# codelock.net
KiCad netlist of a schematic drawn in EAGLE
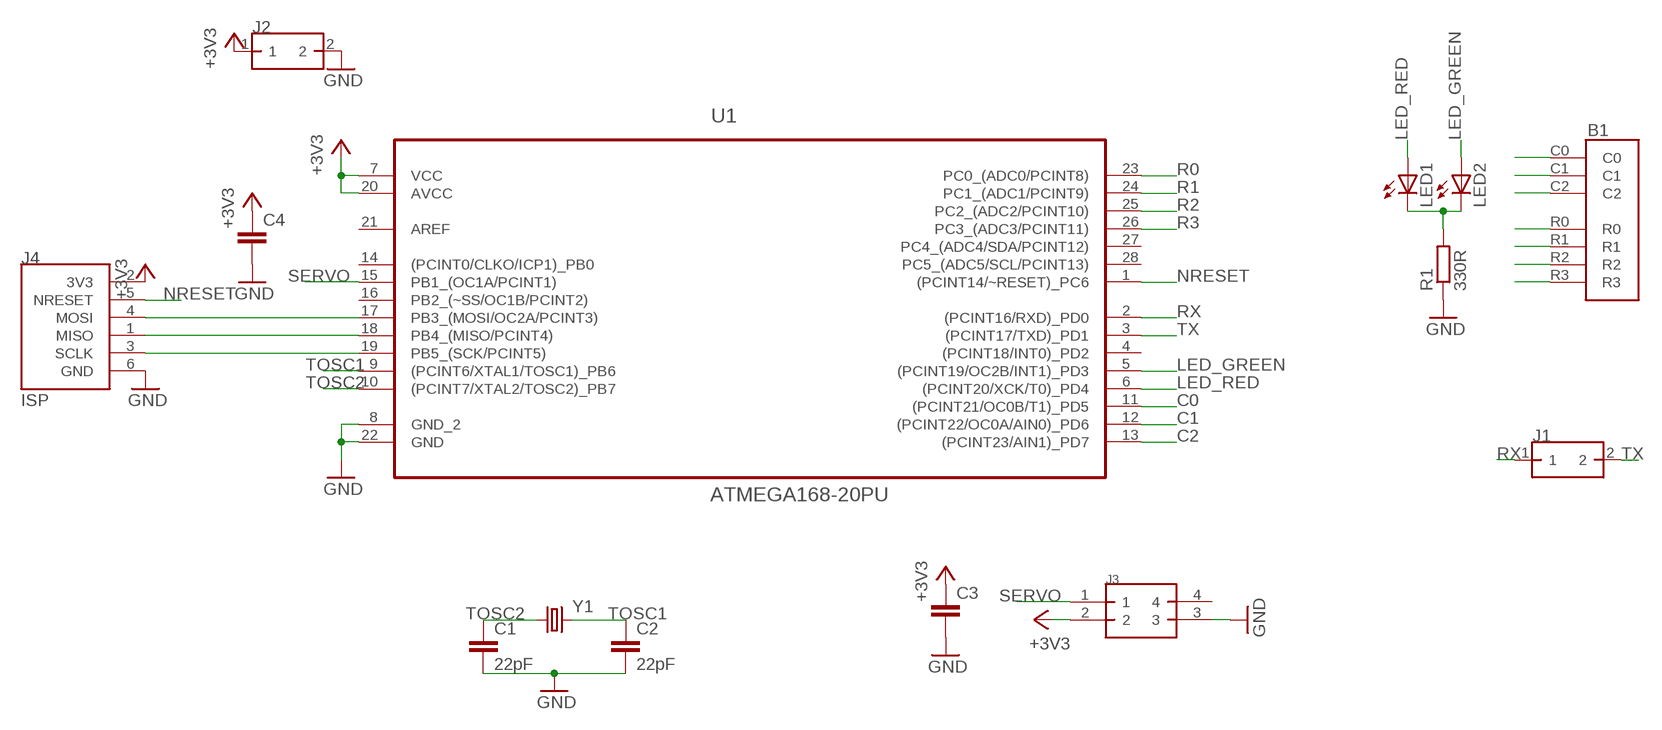
[diagram p0: schematic, sheet 1]

(export (version "E")
  (design (tool "Eeschema 10.0.6"))
  (components
    (comp (ref "B1")
      (value "KEYPAD12")
      (footprint "eagle-import:KEYPAD12")
      (libsource (lib "eagle-import") (part "KEYPAD12"))
    )
    (comp (ref "C1")
      (value "22pF")
      (footprint "eagle-import:C025-024X044")
      (libsource (lib "eagle-import") (part "C-EU025-024X044"))
    )
    (comp (ref "C2")
      (value "22pF")
      (footprint "eagle-import:C025-024X044")
      (libsource (lib "eagle-import") (part "C-EU025-024X044"))
    )
    (comp (ref "C3")
      (value "C-EU025-024X044")
      (footprint "eagle-import:C025-024X044")
      (libsource (lib "eagle-import") (part "C-EU025-024X044"))
    )
    (comp (ref "C4")
      (value "C-EU025-024X044")
      (footprint "eagle-import:C025-024X044")
      (libsource (lib "eagle-import") (part "C-EU025-024X044"))
    )
    (comp (ref "J1")
      (value "1BY2THROUGHHOLE")
      (footprint "eagle-import:1BY2")
      (libsource (lib "eagle-import") (part "1BY2THROUGHHOLE"))
    )
    (comp (ref "J2")
      (value "1BY2THROUGHHOLE")
      (footprint "eagle-import:1BY2")
      (libsource (lib "eagle-import") (part "1BY2THROUGHHOLE"))
    )
    (comp (ref "J3")
      (value "4PIN2.54MM1X4TH")
      (footprint "eagle-import:2.54MM1X4TH")
      (libsource (lib "eagle-import") (part "4PIN2.54MM1X4TH"))
    )
    (comp (ref "J4")
      (value "ISP")
      (footprint "eagle-import:DUALHEAD_TH_6")
      (libsource (lib "eagle-import") (part "ISP"))
    )
    (comp (ref "LED1")
      (value "LED3MM")
      (footprint "eagle-import:LED3MM")
      (libsource (lib "eagle-import") (part "LED3MM"))
    )
    (comp (ref "LED2")
      (value "LED3MM")
      (footprint "eagle-import:LED3MM")
      (libsource (lib "eagle-import") (part "LED3MM"))
    )
    (comp (ref "R1")
      (value "330R")
      (footprint "eagle-import:V234_12")
      (libsource (lib "eagle-import") (part "R12MM"))
    )
    (comp (ref "U1")
      (value "ATMEGA168-20PU")
      (footprint "eagle-import:DIP254P762X457-28")
      (libsource (lib "eagle-import") (part "ATMEGA168-20PU"))
    )
    (comp (ref "Y1")
      (value "CRYSTALHC49US")
      (footprint "eagle-import:HC49US")
      (libsource (lib "eagle-import") (part "CRYSTALHC49US"))
    )
  )
  (nets
    (net (code "1") (name "+3V3") (class "Default")
      (node (ref "C3") (pin "1") (pinfunction "1_1") (pintype "passive"))
      (node (ref "C4") (pin "1") (pinfunction "1_1") (pintype "passive"))
      (node (ref "J2") (pin "1") (pinfunction "1_1") (pintype "bidirectional"))
      (node (ref "J3") (pin "2") (pinfunction "2_2") (pintype "bidirectional"))
      (node (ref "J4") (pin "2") (pinfunction "3V3_2") (pintype "power_in"))
      (node (ref "U1") (pin "20") (pinfunction "AVCC_20") (pintype "power_in"))
      (node (ref "U1") (pin "7") (pinfunction "VCC_7") (pintype "power_in"))
    )
    (net (code "2") (name "/C0") (class "Default")
      (node (ref "B1") (pin "C0") (pinfunction "C0_C0") (pintype "bidirectional"))
      (node (ref "U1") (pin "11") (pinfunction "(PCINT21/OC0B/T1)_PD5_11") (pintype "bidirectional"))
    )
    (net (code "3") (name "/C1") (class "Default")
      (node (ref "B1") (pin "C1") (pinfunction "C1_C1") (pintype "bidirectional"))
      (node (ref "U1") (pin "12") (pinfunction "(PCINT22/OC0A/AIN0)_PD6_12") (pintype "bidirectional"))
    )
    (net (code "4") (name "/C2") (class "Default")
      (node (ref "B1") (pin "C2") (pinfunction "C2_C2") (pintype "bidirectional"))
      (node (ref "U1") (pin "13") (pinfunction "(PCINT23/AIN1)_PD7_13") (pintype "bidirectional"))
    )
    (net (code "5") (name "/LED_GREEN") (class "Default")
      (node (ref "LED2") (pin "A") (pinfunction "A_A") (pintype "passive"))
      (node (ref "U1") (pin "5") (pinfunction "(PCINT19/OC2B/INT1)_PD3_5") (pintype "bidirectional"))
    )
    (net (code "6") (name "/LED_RED") (class "Default")
      (node (ref "LED1") (pin "A") (pinfunction "A_A") (pintype "passive"))
      (node (ref "U1") (pin "6") (pinfunction "(PCINT20/XCK/T0)_PD4_6") (pintype "bidirectional"))
    )
    (net (code "7") (name "/NRESET") (class "Default")
      (node (ref "J4") (pin "5") (pinfunction "NRESET_5") (pintype "output"))
      (node (ref "U1") (pin "1") (pinfunction "(PCINT14/~{RESET})_PC6_1") (pintype "bidirectional"))
    )
    (net (code "8") (name "/R0") (class "Default")
      (node (ref "B1") (pin "R0") (pinfunction "R0_R0") (pintype "bidirectional"))
      (node (ref "U1") (pin "23") (pinfunction "PC0_(ADC0/PCINT8)_23") (pintype "bidirectional"))
    )
    (net (code "9") (name "/R1") (class "Default")
      (node (ref "B1") (pin "R1") (pinfunction "R1_R1") (pintype "bidirectional"))
      (node (ref "U1") (pin "24") (pinfunction "PC1_(ADC1/PCINT9)_24") (pintype "bidirectional"))
    )
    (net (code "10") (name "/R2") (class "Default")
      (node (ref "B1") (pin "R2") (pinfunction "R2_R2") (pintype "bidirectional"))
      (node (ref "U1") (pin "25") (pinfunction "PC2_(ADC2/PCINT10)_25") (pintype "bidirectional"))
    )
    (net (code "11") (name "/R3") (class "Default")
      (node (ref "B1") (pin "R3") (pinfunction "R3_R3") (pintype "bidirectional"))
      (node (ref "U1") (pin "26") (pinfunction "PC3_(ADC3/PCINT11)_26") (pintype "bidirectional"))
    )
    (net (code "12") (name "/RX") (class "Default")
      (node (ref "J1") (pin "1") (pinfunction "1_1") (pintype "bidirectional"))
      (node (ref "U1") (pin "2") (pinfunction "(PCINT16/RXD)_PD0_2") (pintype "bidirectional"))
    )
    (net (code "13") (name "/SERVO") (class "Default")
      (node (ref "J3") (pin "1") (pinfunction "1_1") (pintype "bidirectional"))
      (node (ref "U1") (pin "15") (pinfunction "PB1_(OC1A/PCINT1)_15") (pintype "bidirectional"))
    )
    (net (code "14") (name "/TOSC1") (class "Default")
      (node (ref "C2") (pin "1") (pinfunction "1_1") (pintype "passive"))
      (node (ref "U1") (pin "9") (pinfunction "(PCINT6/XTAL1/TOSC1)_PB6_9") (pintype "bidirectional"))
      (node (ref "Y1") (pin "2") (pinfunction "2_2") (pintype "passive"))
    )
    (net (code "15") (name "/TOSC2") (class "Default")
      (node (ref "C1") (pin "1") (pinfunction "1_1") (pintype "passive"))
      (node (ref "U1") (pin "10") (pinfunction "(PCINT7/XTAL2/TOSC2)_PB7_10") (pintype "bidirectional"))
      (node (ref "Y1") (pin "1") (pinfunction "1_1") (pintype "passive"))
    )
    (net (code "16") (name "/TX") (class "Default")
      (node (ref "J1") (pin "2") (pinfunction "2_2") (pintype "bidirectional"))
      (node (ref "U1") (pin "3") (pinfunction "(PCINT17/TXD)_PD1_3") (pintype "bidirectional"))
    )
    (net (code "17") (name "GND") (class "Default")
      (node (ref "C1") (pin "2") (pinfunction "2_2") (pintype "passive"))
      (node (ref "C2") (pin "2") (pinfunction "2_2") (pintype "passive"))
      (node (ref "C3") (pin "2") (pinfunction "2_2") (pintype "passive"))
      (node (ref "C4") (pin "2") (pinfunction "2_2") (pintype "passive"))
      (node (ref "J2") (pin "2") (pinfunction "2_2") (pintype "bidirectional"))
      (node (ref "J3") (pin "3") (pinfunction "3_3") (pintype "bidirectional"))
      (node (ref "J4") (pin "6") (pinfunction "GND_6") (pintype "power_in"))
      (node (ref "R1") (pin "1") (pinfunction "1_1") (pintype "passive"))
      (node (ref "U1") (pin "22") (pinfunction "GND_22") (pintype "passive"))
      (node (ref "U1") (pin "8") (pinfunction "GND_2_8") (pintype "passive"))
    )
    (net (code "18") (name "Net-(J4-MISO)") (class "Default")
      (node (ref "J4") (pin "1") (pinfunction "MISO_1") (pintype "bidirectional"))
      (node (ref "U1") (pin "18") (pinfunction "PB4_(MISO/PCINT4)_18") (pintype "bidirectional"))
    )
    (net (code "19") (name "Net-(J4-MOSI)") (class "Default")
      (node (ref "J4") (pin "4") (pinfunction "MOSI_4") (pintype "output"))
      (node (ref "U1") (pin "17") (pinfunction "PB3_(MOSI/OC2A/PCINT3)_17") (pintype "bidirectional"))
    )
    (net (code "20") (name "Net-(J4-SCLK)") (class "Default")
      (node (ref "J4") (pin "3") (pinfunction "SCLK_3") (pintype "output"))
      (node (ref "U1") (pin "19") (pinfunction "PB5_(SCK/PCINT5)_19") (pintype "bidirectional"))
    )
    (net (code "21") (name "Net-(LED1-C)") (class "Default")
      (node (ref "LED1") (pin "K") (pinfunction "C_K") (pintype "passive"))
      (node (ref "LED2") (pin "K") (pinfunction "C_K") (pintype "passive"))
      (node (ref "R1") (pin "2") (pinfunction "2_2") (pintype "passive"))
    )
    (net (code "22") (name "unconnected-(J3-Pad4)") (class "Default")
      (node (ref "J3") (pin "4") (pinfunction "4_4") (pintype "bidirectional"))
    )
    (net (code "23") (name "unconnected-(U1-(PCINT0{slash}CLKO{slash}ICP1)_PB0-Pad14)") (class "Default")
      (node (ref "U1") (pin "14") (pinfunction "(PCINT0/CLKO/ICP1)_PB0_14") (pintype "bidirectional"))
    )
    (net (code "24") (name "unconnected-(U1-(PCINT18{slash}INT0)_PD2-Pad4)") (class "Default")
      (node (ref "U1") (pin "4") (pinfunction "(PCINT18/INT0)_PD2_4") (pintype "bidirectional"))
    )
    (net (code "25") (name "unconnected-(U1-AREF-Pad21)") (class "Default")
      (node (ref "U1") (pin "21") (pinfunction "AREF_21") (pintype "input"))
    )
    (net (code "26") (name "unconnected-(U1-PB2_(~{SS{slash}OC1B{slash}PCINT2})-Pad16)") (class "Default")
      (node (ref "U1") (pin "16") (pinfunction "PB2_(~{SS/OC1B/PCINT2})_16") (pintype "bidirectional"))
    )
    (net (code "27") (name "unconnected-(U1-PC4_(ADC4{slash}SDA{slash}PCINT12)-Pad27)") (class "Default")
      (node (ref "U1") (pin "27") (pinfunction "PC4_(ADC4/SDA/PCINT12)_27") (pintype "bidirectional"))
    )
    (net (code "28") (name "unconnected-(U1-PC5_(ADC5{slash}SCL{slash}PCINT13)-Pad28)") (class "Default")
      (node (ref "U1") (pin "28") (pinfunction "PC5_(ADC5/SCL/PCINT13)_28") (pintype "bidirectional"))
    )
  )
)
